# AirPurity_V1.net
KiCad netlist of a schematic drawn in Altium Designer
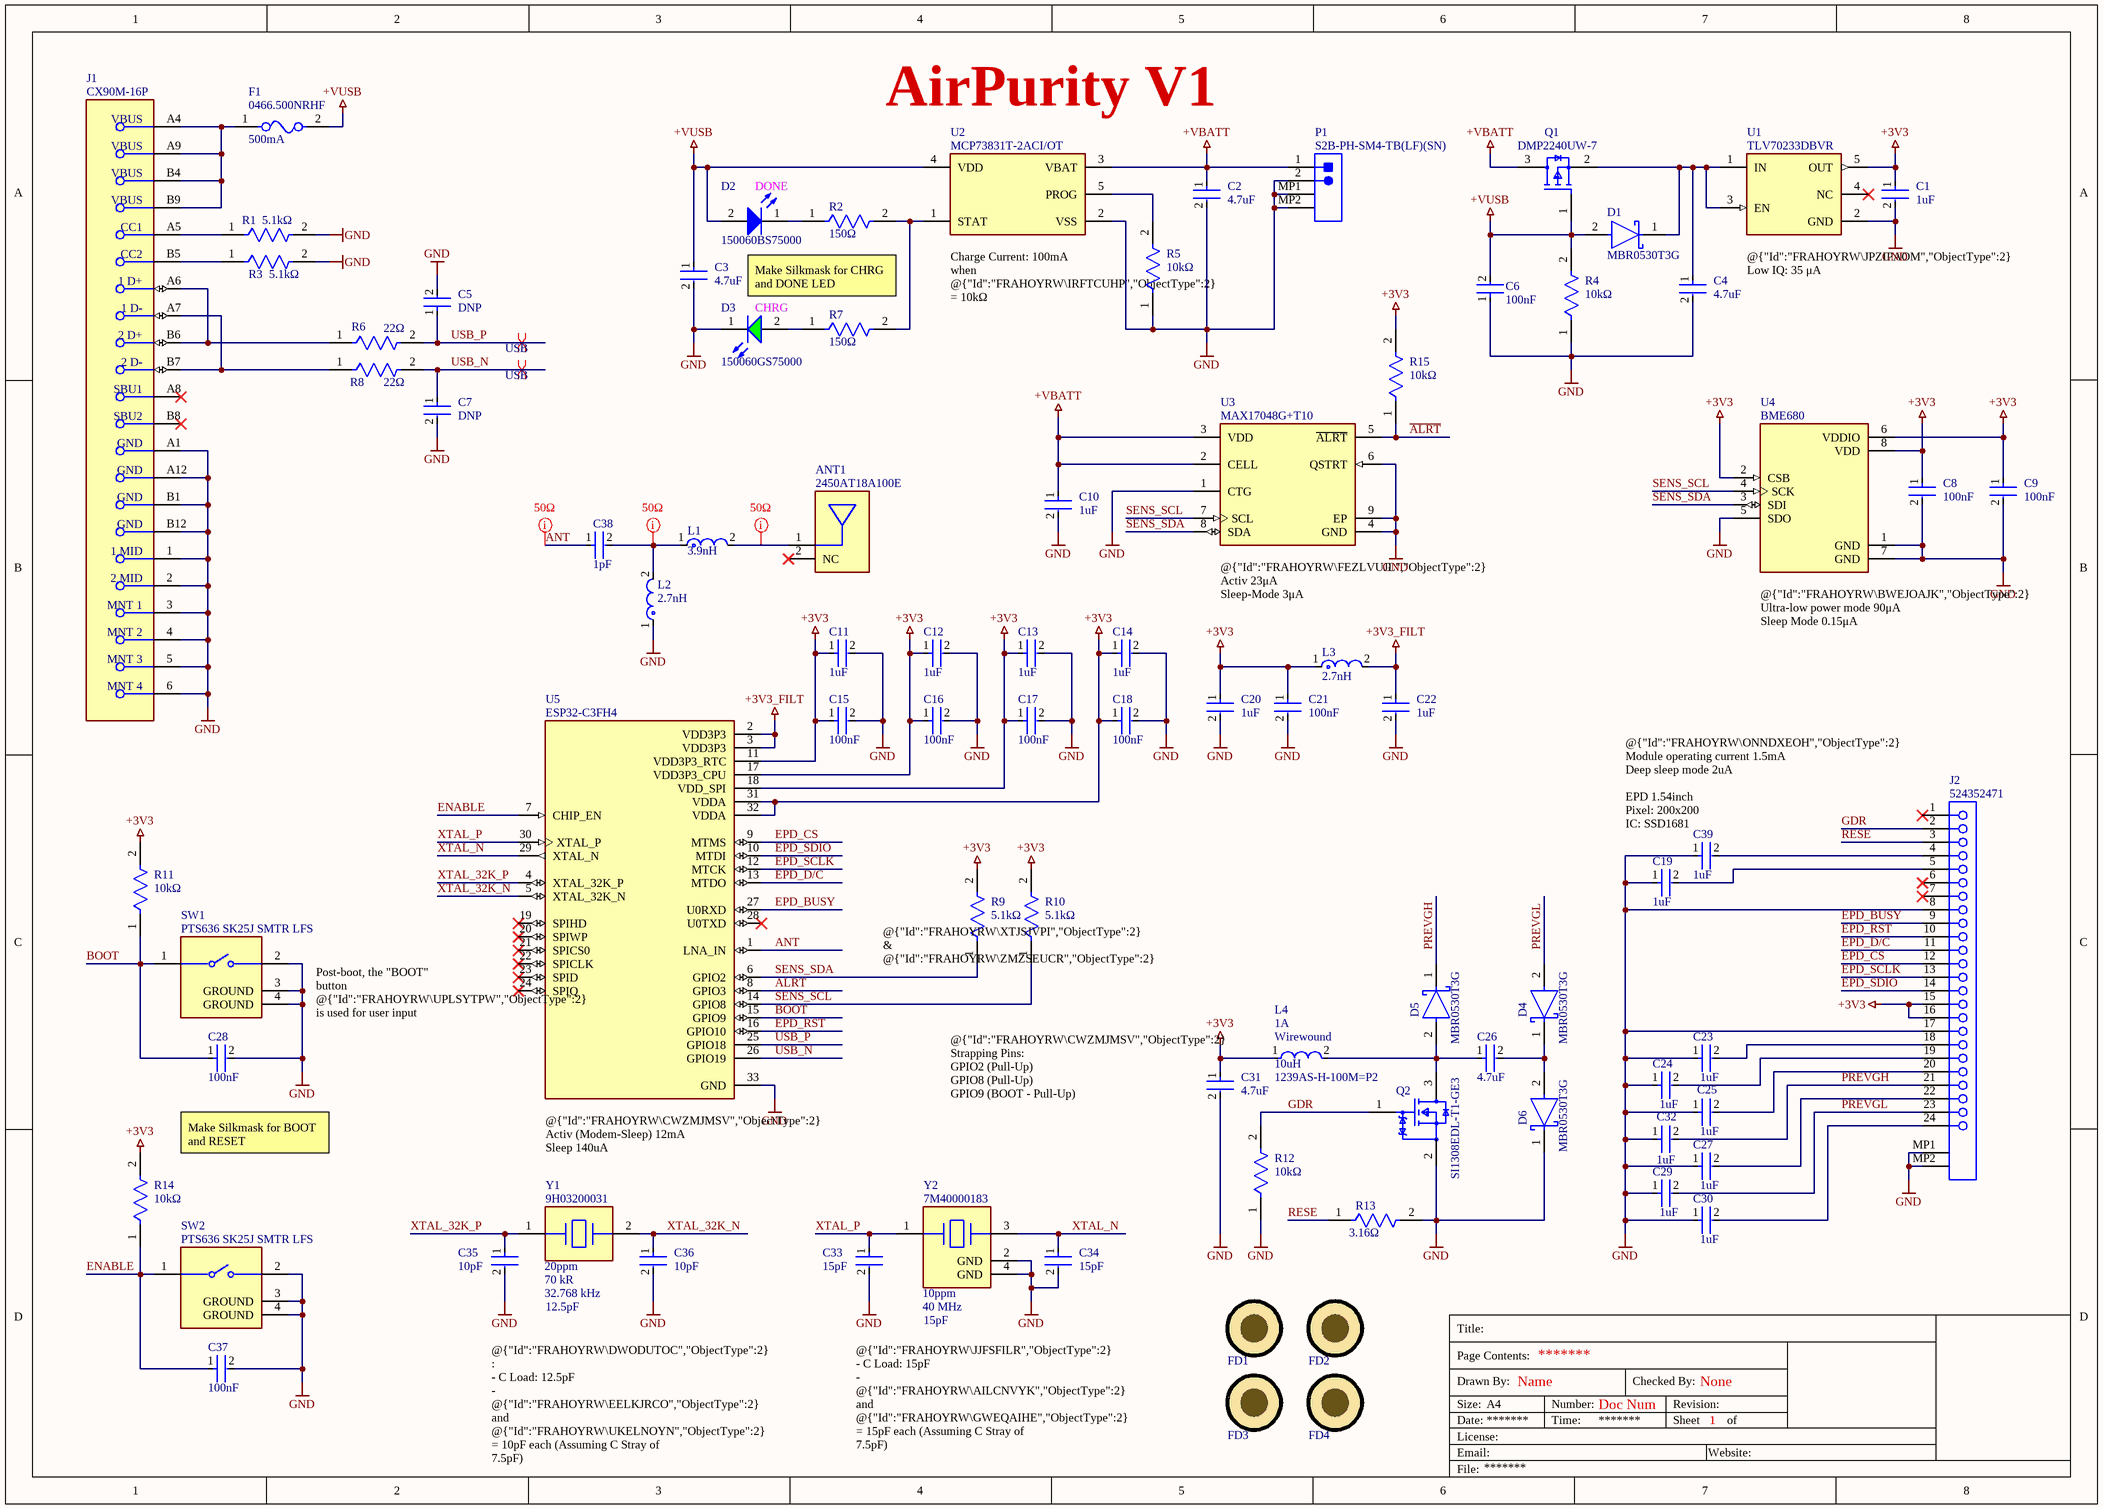
[diagram p0: AirPurity_V1.SchDoc]

(export (version "E")
  (design (tool "Eeschema 10.0.6"))
  (components
    (comp (ref "ANT1")
      (value "2450AT18A100")
      (footprint "FP-2450AT18A0100001E-MFG")
      (description "Chip Antenna 0.5dBi 2.4GHz 2W 1206")
      (fields
        (field (name "LCSC PART NUMBER") "C89334")
        (field (name "MANUFACTURER PART NUMBER") "2450AT18A100E")
      )
      (libsource (lib "Library") (part "2450AT18A100"))
    )
    (comp (ref "C1")
      (value "GRM155R61E105KA12D")
      (footprint "GRM155-0402-MFG")
      (description "1uF X5R 0402 Multilayer Ceramic Capacitor")
      (fields (field (name "LCSC PART NUMBER") "C77009") (field (name "CAPACITANCE") "1uF"))
      (libsource (lib "Library") (part "GRM155R61E105KA12D"))
    )
    (comp (ref "C2")
      (value "GRM155R61E475ME15D")
      (footprint "GRM155-0402-MFG")
      (description "4.7uF X5R 0402 Multilayer Ceramic Capacitor")
      (fields (field (name "LCSC PART NUMBER") "C2858031") (field (name "CAPACITANCE") "4.7uF"))
      (libsource (lib "Library") (part "GRM155R61E475ME15D"))
    )
    (comp (ref "C3")
      (value "GRM155R61E475ME15D")
      (footprint "GRM155-0402-MFG")
      (description "4.7uF X5R 0402 Multilayer Ceramic Capacitor")
      (fields (field (name "LCSC PART NUMBER") "C2858031") (field (name "CAPACITANCE") "4.7uF"))
      (libsource (lib "Library") (part "GRM155R61E475ME15D"))
    )
    (comp (ref "C4")
      (value "GRM155R61E475ME15D")
      (footprint "GRM155-0402-MFG")
      (description "4.7uF X5R 0402 Multilayer Ceramic Capacitor")
      (fields (field (name "LCSC PART NUMBER") "C2858031") (field (name "CAPACITANCE") "4.7uF"))
      (libsource (lib "Library") (part "GRM155R61E475ME15D"))
    )
    (comp (ref "C5")
      (value "GRM0335C1H150FA01D")
      (footprint "GRM033-0201-MFG")
      (description "15pF C0G 0201 Multilayer Ceramic Capacitor")
      (fields (field (name "LCSC PART NUMBER") "C237567") (field (name "CAPACITANCE") "DNP"))
      (libsource (lib "Library") (part "GRM0335C1H150FA01D"))
    )
    (comp (ref "C6")
      (value "GRM033R61A104KE15D")
      (footprint "GRM033-0201-MFG")
      (description "100nF X5R 0201 Multilayer Ceramic Capacitor")
      (fields (field (name "LCSC PART NUMBER") "C76934") (field (name "CAPACITANCE") "100nF"))
      (libsource (lib "Library") (part "GRM033R61A104KE15D"))
    )
    (comp (ref "C7")
      (value "GRM0335C1H150FA01D")
      (footprint "GRM033-0201-MFG")
      (description "15pF C0G 0201 Multilayer Ceramic Capacitor")
      (fields (field (name "LCSC PART NUMBER") "C237567") (field (name "CAPACITANCE") "DNP"))
      (libsource (lib "Library") (part "GRM0335C1H150FA01D"))
    )
    (comp (ref "C8")
      (value "GRM033R61A104KE15D")
      (footprint "GRM033-0201-MFG")
      (description "100nF X5R 0201 Multilayer Ceramic Capacitor")
      (fields (field (name "LCSC PART NUMBER") "C76934") (field (name "CAPACITANCE") "100nF"))
      (libsource (lib "Library") (part "GRM033R61A104KE15D"))
    )
    (comp (ref "C9")
      (value "GRM033R61A104KE15D")
      (footprint "GRM033-0201-MFG")
      (description "100nF X5R 0201 Multilayer Ceramic Capacitor")
      (fields (field (name "LCSC PART NUMBER") "C76934") (field (name "CAPACITANCE") "100nF"))
      (libsource (lib "Library") (part "GRM033R61A104KE15D"))
    )
    (comp (ref "C10")
      (value "GRM155R61E105KA12D")
      (footprint "GRM155-0402-MFG")
      (description "1uF X5R 0402 Multilayer Ceramic Capacitor")
      (fields (field (name "LCSC PART NUMBER") "C77009") (field (name "CAPACITANCE") "1uF"))
      (libsource (lib "Library") (part "GRM155R61E105KA12D"))
    )
    (comp (ref "C11")
      (value "GRM155R61E105KA12D")
      (footprint "GRM155-0402-MFG")
      (description "1uF X5R 0402 Multilayer Ceramic Capacitor")
      (fields (field (name "LCSC PART NUMBER") "C77009") (field (name "CAPACITANCE") "1uF"))
      (libsource (lib "Library") (part "GRM155R61E105KA12D"))
    )
    (comp (ref "C12")
      (value "GRM155R61E105KA12D")
      (footprint "GRM155-0402-MFG")
      (description "1uF X5R 0402 Multilayer Ceramic Capacitor")
      (fields (field (name "LCSC PART NUMBER") "C77009") (field (name "CAPACITANCE") "1uF"))
      (libsource (lib "Library") (part "GRM155R61E105KA12D"))
    )
    (comp (ref "C13")
      (value "GRM155R61E105KA12D")
      (footprint "GRM155-0402-MFG")
      (description "1uF X5R 0402 Multilayer Ceramic Capacitor")
      (fields (field (name "LCSC PART NUMBER") "C77009") (field (name "CAPACITANCE") "1uF"))
      (libsource (lib "Library") (part "GRM155R61E105KA12D"))
    )
    (comp (ref "C14")
      (value "GRM155R61E105KA12D")
      (footprint "GRM155-0402-MFG")
      (description "1uF X5R 0402 Multilayer Ceramic Capacitor")
      (fields (field (name "LCSC PART NUMBER") "C77009") (field (name "CAPACITANCE") "1uF"))
      (libsource (lib "Library") (part "GRM155R61E105KA12D"))
    )
    (comp (ref "C15")
      (value "GRM033R61A104KE15D")
      (footprint "GRM033-0201-MFG")
      (description "100nF X5R 0201 Multilayer Ceramic Capacitor")
      (fields (field (name "LCSC PART NUMBER") "C76934") (field (name "CAPACITANCE") "100nF"))
      (libsource (lib "Library") (part "GRM033R61A104KE15D"))
    )
    (comp (ref "C16")
      (value "GRM033R61A104KE15D")
      (footprint "GRM033-0201-MFG")
      (description "100nF X5R 0201 Multilayer Ceramic Capacitor")
      (fields (field (name "LCSC PART NUMBER") "C76934") (field (name "CAPACITANCE") "100nF"))
      (libsource (lib "Library") (part "GRM033R61A104KE15D"))
    )
    (comp (ref "C17")
      (value "GRM033R61A104KE15D")
      (footprint "GRM033-0201-MFG")
      (description "100nF X5R 0201 Multilayer Ceramic Capacitor")
      (fields (field (name "LCSC PART NUMBER") "C76934") (field (name "CAPACITANCE") "100nF"))
      (libsource (lib "Library") (part "GRM033R61A104KE15D"))
    )
    (comp (ref "C18")
      (value "GRM033R61A104KE15D")
      (footprint "GRM033-0201-MFG")
      (description "100nF X5R 0201 Multilayer Ceramic Capacitor")
      (fields (field (name "LCSC PART NUMBER") "C76934") (field (name "CAPACITANCE") "100nF"))
      (libsource (lib "Library") (part "GRM033R61A104KE15D"))
    )
    (comp (ref "C19")
      (value "GRM155R61E105KA12D")
      (footprint "GRM155-0402-MFG")
      (description "1uF X5R 0402 Multilayer Ceramic Capacitor")
      (fields (field (name "LCSC PART NUMBER") "C77009") (field (name "CAPACITANCE") "1uF"))
      (libsource (lib "Library") (part "GRM155R61E105KA12D"))
    )
    (comp (ref "C20")
      (value "GRM155R61E105KA12D")
      (footprint "GRM155-0402-MFG")
      (description "1uF X5R 0402 Multilayer Ceramic Capacitor")
      (fields (field (name "LCSC PART NUMBER") "C77009") (field (name "CAPACITANCE") "1uF"))
      (libsource (lib "Library") (part "GRM155R61E105KA12D"))
    )
    (comp (ref "C21")
      (value "GRM033R61A104KE15D")
      (footprint "GRM033-0201-MFG")
      (description "100nF X5R 0201 Multilayer Ceramic Capacitor")
      (fields (field (name "LCSC PART NUMBER") "C76934") (field (name "CAPACITANCE") "100nF"))
      (libsource (lib "Library") (part "GRM033R61A104KE15D"))
    )
    (comp (ref "C22")
      (value "GRM155R61E105KA12D")
      (footprint "GRM155-0402-MFG")
      (description "1uF X5R 0402 Multilayer Ceramic Capacitor")
      (fields (field (name "LCSC PART NUMBER") "C77009") (field (name "CAPACITANCE") "1uF"))
      (libsource (lib "Library") (part "GRM155R61E105KA12D"))
    )
    (comp (ref "C23")
      (value "GRM155R61E105KA12D")
      (footprint "GRM155-0402-MFG")
      (description "1uF X5R 0402 Multilayer Ceramic Capacitor")
      (fields (field (name "LCSC PART NUMBER") "C77009") (field (name "CAPACITANCE") "1uF"))
      (libsource (lib "Library") (part "GRM155R61E105KA12D"))
    )
    (comp (ref "C24")
      (value "GRM155R61E105KA12D")
      (footprint "GRM155-0402-MFG")
      (description "1uF X5R 0402 Multilayer Ceramic Capacitor")
      (fields (field (name "LCSC PART NUMBER") "C77009") (field (name "CAPACITANCE") "1uF"))
      (libsource (lib "Library") (part "GRM155R61E105KA12D"))
    )
    (comp (ref "C25")
      (value "GRM155R61E105KA12D")
      (footprint "GRM155-0402-MFG")
      (description "1uF X5R 0402 Multilayer Ceramic Capacitor")
      (fields (field (name "LCSC PART NUMBER") "C77009") (field (name "CAPACITANCE") "1uF"))
      (libsource (lib "Library") (part "GRM155R61E105KA12D"))
    )
    (comp (ref "C26")
      (value "GRM155R61E475ME15D")
      (footprint "GRM155-0402-MFG")
      (description "4.7uF X5R 0402 Multilayer Ceramic Capacitor")
      (fields (field (name "LCSC PART NUMBER") "C2858031") (field (name "CAPACITANCE") "4.7uF"))
      (libsource (lib "Library") (part "GRM155R61E475ME15D"))
    )
    (comp (ref "C27")
      (value "GRM155R61E105KA12D")
      (footprint "GRM155-0402-MFG")
      (description "1uF X5R 0402 Multilayer Ceramic Capacitor")
      (fields (field (name "LCSC PART NUMBER") "C77009") (field (name "CAPACITANCE") "1uF"))
      (libsource (lib "Library") (part "GRM155R61E105KA12D"))
    )
    (comp (ref "C28")
      (value "GRM033R61A104KE15D")
      (footprint "GRM033-0201-MFG")
      (description "100nF X5R 0201 Multilayer Ceramic Capacitor")
      (fields (field (name "LCSC PART NUMBER") "C76934") (field (name "CAPACITANCE") "100nF"))
      (libsource (lib "Library") (part "GRM033R61A104KE15D"))
    )
    (comp (ref "C29")
      (value "GRM155R61E105KA12D")
      (footprint "GRM155-0402-MFG")
      (description "1uF X5R 0402 Multilayer Ceramic Capacitor")
      (fields (field (name "LCSC PART NUMBER") "C77009") (field (name "CAPACITANCE") "1uF"))
      (libsource (lib "Library") (part "GRM155R61E105KA12D"))
    )
    (comp (ref "C30")
      (value "GRM155R61E105KA12D")
      (footprint "GRM155-0402-MFG")
      (description "1uF X5R 0402 Multilayer Ceramic Capacitor")
      (fields (field (name "LCSC PART NUMBER") "C77009") (field (name "CAPACITANCE") "1uF"))
      (libsource (lib "Library") (part "GRM155R61E105KA12D"))
    )
    (comp (ref "C31")
      (value "GRM155R61E475ME15D")
      (footprint "GRM155-0402-MFG")
      (description "4.7uF X5R 0402 Multilayer Ceramic Capacitor")
      (fields (field (name "LCSC PART NUMBER") "C2858031") (field (name "CAPACITANCE") "4.7uF"))
      (libsource (lib "Library") (part "GRM155R61E475ME15D"))
    )
    (comp (ref "C32")
      (value "GRM155R61E105KA12D")
      (footprint "GRM155-0402-MFG")
      (description "1uF X5R 0402 Multilayer Ceramic Capacitor")
      (fields (field (name "LCSC PART NUMBER") "C77009") (field (name "CAPACITANCE") "1uF"))
      (libsource (lib "Library") (part "GRM155R61E105KA12D"))
    )
    (comp (ref "C33")
      (value "GRM0335C1H150FA01D")
      (footprint "GRM033-0201-MFG")
      (description "15pF C0G 0201 Multilayer Ceramic Capacitor")
      (fields (field (name "LCSC PART NUMBER") "C237567") (field (name "CAPACITANCE") "15pF"))
      (libsource (lib "Library") (part "GRM0335C1H150FA01D"))
    )
    (comp (ref "C34")
      (value "GRM0335C1H150FA01D")
      (footprint "GRM033-0201-MFG")
      (description "15pF C0G 0201 Multilayer Ceramic Capacitor")
      (fields (field (name "LCSC PART NUMBER") "C237567") (field (name "CAPACITANCE") "15pF"))
      (libsource (lib "Library") (part "GRM0335C1H150FA01D"))
    )
    (comp (ref "C35")
      (value "GRM0335C1H100JA01D")
      (footprint "GRM033-0201-MFG")
      (description "10pF C0G 0201 Multilayer Ceramic Capacitor")
      (fields (field (name "LCSC PART NUMBER") "C76921") (field (name "CAPACITANCE") "10pF"))
      (libsource (lib "Library") (part "GRM0335C1H100JA01D"))
    )
    (comp (ref "C36")
      (value "GRM0335C1H100JA01D")
      (footprint "GRM033-0201-MFG")
      (description "10pF C0G 0201 Multilayer Ceramic Capacitor")
      (fields (field (name "LCSC PART NUMBER") "C76921") (field (name "CAPACITANCE") "10pF"))
      (libsource (lib "Library") (part "GRM0335C1H100JA01D"))
    )
    (comp (ref "C37")
      (value "GRM033R61A104KE15D")
      (footprint "GRM033-0201-MFG")
      (description "100nF X5R 0201 Multilayer Ceramic Capacitor")
      (fields (field (name "LCSC PART NUMBER") "C76934") (field (name "CAPACITANCE") "100nF"))
      (libsource (lib "Library") (part "GRM033R61A104KE15D"))
    )
    (comp (ref "C38")
      (value "GRM0335C1H1R0BA01D")
      (footprint "GRM033-0201-MFG")
      (description "1pF C0G 0201 Multilayer Ceramic Capacitor")
      (fields (field (name "LCSC PART NUMBER") "C85893") (field (name "CAPACITANCE") "1pF"))
      (libsource (lib "Library") (part "GRM0335C1H1R0BA01D"))
    )
    (comp (ref "C39")
      (value "GRM155R61E105KA12D")
      (footprint "GRM155-0402-MFG")
      (description "1uF X5R 0402 Multilayer Ceramic Capacitor")
      (fields (field (name "LCSC PART NUMBER") "C77009") (field (name "CAPACITANCE") "1uF"))
      (libsource (lib "Library") (part "GRM155R61E105KA12D"))
    )
    (comp (ref "D1")
      (value "MBR0530T3G")
      (footprint "425-04-MFG")
      (description "Schottky Barrier Diodes")
      (fields
        (field (name "LCSC PART NUMBER") "C236079")
        (field (name "MANUFACTURER PART NUMBER") "MBR0530T3G")
      )
      (libsource (lib "Library") (part "MBR0530T3G"))
    )
    (comp (ref "D2")
      (value "150060BS75000")
      (footprint "0603_150060xx75000")
      (description "LED Blue 3.2V 0603")
      (fields
        (field (name "LCSC PART NUMBER") "C5197644")
        (field (name "MANUFACTURER PART NUMBER") "150060BS75000")
      )
      (libsource (lib "Library") (part "150060BS75000"))
    )
    (comp (ref "D3")
      (value "150060GS75000")
      (footprint "0603_150060xx75000")
      (description "LED Emerald 3.2V 0603")
      (fields
        (field (name "LCSC PART NUMBER") "C5252984")
        (field (name "MANUFACTURER PART NUMBER") "150060GS75000")
      )
      (libsource (lib "Library") (part "150060GS75000"))
    )
    (comp (ref "D4")
      (value "MBR0530T3G")
      (footprint "425-04-MFG")
      (description "Schottky Barrier Diodes")
      (fields
        (field (name "LCSC PART NUMBER") "C236079")
        (field (name "MANUFACTURER PART NUMBER") "MBR0530T3G")
      )
      (libsource (lib "Library") (part "MBR0530T3G"))
    )
    (comp (ref "D5")
      (value "MBR0530T3G")
      (footprint "425-04-MFG")
      (description "Schottky Barrier Diodes")
      (fields
        (field (name "LCSC PART NUMBER") "C236079")
        (field (name "MANUFACTURER PART NUMBER") "MBR0530T3G")
      )
      (libsource (lib "Library") (part "MBR0530T3G"))
    )
    (comp (ref "D6")
      (value "MBR0530T3G")
      (footprint "425-04-MFG")
      (description "Schottky Barrier Diodes")
      (fields
        (field (name "LCSC PART NUMBER") "C236079")
        (field (name "MANUFACTURER PART NUMBER") "MBR0530T3G")
      )
      (libsource (lib "Library") (part "MBR0530T3G"))
    )
    (comp (ref "F1")
      (value "0466.500NRHF")
      (footprint "0466-MFG")
      (description "Fuse 500mA")
      (fields
        (field (name "LCSC PART NUMBER") "C151133")
        (field (name "MANUFACTURER PART NUMBER") "0466.500NRHF")
        (field (name "CURRENT") "500mA")
      )
      (libsource (lib "Library") (part "0466.500NRHF"))
    )
    (comp (ref "FD1")
      (value "Fiducial")
      (footprint "FIDUCIAL-1MM")
      (libsource (lib "Library") (part "Fiducial"))
    )
    (comp (ref "FD2")
      (value "Fiducial")
      (footprint "FIDUCIAL-1MM")
      (libsource (lib "Library") (part "Fiducial"))
    )
    (comp (ref "FD3")
      (value "Fiducial")
      (footprint "FIDUCIAL-1MM")
      (libsource (lib "Library") (part "Fiducial"))
    )
    (comp (ref "FD4")
      (value "Fiducial")
      (footprint "FIDUCIAL-1MM")
      (libsource (lib "Library") (part "Fiducial"))
    )
    (comp (ref "J1")
      (value "CX90M-16P")
      (footprint "CX90M-16P-MFG")
      (description "Connector USB2.0 TYPE-C 16POS")
      (fields
        (field (name "LCSC PART NUMBER") "C2889324")
        (field (name "MANUFACTURER PART NUMBER") "CX90M-16P")
      )
      (libsource (lib "Library") (part "CX90M-16P"))
    )
    (comp (ref "J2")
      (value "524352471")
      (footprint "52435-2471")
      (description "FPC Connector, 2.0 mm, 0.5 mm, Right Angle")
      (fields
        (field (name "LCSC PART NUMBER") "C122394")
        (field (name "MANUFACTURER PART NUMBER") "524352471")
      )
      (libsource (lib "Library") (part "524352471"))
    )
    (comp (ref "L1")
      (value "LQP03TN3N9B02D")
      (footprint "LQP03TG-MFG")
      (description "Inductor 3.9nH")
      (fields (field (name "LCSC PART NUMBER") "C77115") (field (name "INDUCTANCE") "3.9nH"))
      (libsource (lib "Library") (part "LQP03TN3N9B02D"))
    )
    (comp (ref "L2")
      (value "LQP03TG2N7C02D")
      (footprint "LQP03TG-MFG")
      (description "Inductor 2.7nH")
      (fields (field (name "LCSC PART NUMBER") "C337946") (field (name "INDUCTANCE") "2.7nH"))
      (libsource (lib "Library") (part "LQP03TG2N7C02D"))
    )
    (comp (ref "L3")
      (value "LQP03TG2N7C02D")
      (footprint "LQP03TG-MFG")
      (description "Inductor 2.7nH")
      (fields (field (name "LCSC PART NUMBER") "C337946") (field (name "INDUCTANCE") "2.7nH"))
      (libsource (lib "Library") (part "LQP03TG2N7C02D"))
    )
    (comp (ref "L4")
      (value "1239AS-H-100M=P2")
      (footprint "DFE252012C-MFG")
      (description "Inductor 10uH")
      (fields
        (field (name "LCSC PART NUMBER") "C237599")
        (field (name "CURRENT RATING") "1A")
        (field (name "RESISTOR TYPE") "Wirewound")
        (field (name "INDUCTANCE") "10uH")
        (field (name "MANUFACTURER PART NUMBER") "1239AS-H-100M=P2")
      )
      (libsource (lib "Library") (part "1239AS-H-100M=P2"))
    )
    (comp (ref "P1")
      (value "S2B-PH-SM4-TB(LF)(SN)")
      (footprint "JST- S2B-PH-SM4-TB(LF)(SN)")
      (description "Male Header, Pitch 2 mm, 1 x 2 Position")
      (fields
        (field (name "LCSC PART NUMBER") "C295747")
        (field (name "MANUFACTURER PART NUMBER") "S2B-PH-SM4-TB(LF)(SN)")
      )
      (libsource (lib "Library") (part "S2B-PH-SM4-TB(LF)(SN)"))
    )
    (comp (ref "Q1")
      (value "DMP2240UW-7")
      (footprint "SOT323-MFG")
      (description "MOSFET P-Channel")
      (fields
        (field (name "LCSC PART NUMBER") "C459548")
        (field (name "MANUFACTURER PART NUMBER") "DMP2240UW-7")
      )
      (libsource (lib "Library") (part "DMP2240UW-7"))
    )
    (comp (ref "Q2")
      (value "SI1308EDL-T1-GE3")
      (footprint "5549-MFG")
      (description "MOSFET N-Channel")
      (fields
        (field (name "LCSC PART NUMBER") "C469327")
        (field (name "MANUFACTURER PART NUMBER") "SI1308EDL-T1-GE3")
      )
      (libsource (lib "Library") (part "SI1308EDL-T1-GE3"))
    )
    (comp (ref "R1")
      (value "RC0402FR-075K1L")
      (footprint "RC0402-MFG")
      (description "5.1kΩ 0402 Chip Resistor")
      (fields (field (name "LCSC PART NUMBER") "C105872") (field (name "RESISTANCE") "5.1kΩ"))
      (libsource (lib "Library") (part "RC0402FR-075K1L"))
    )
    (comp (ref "R2")
      (value "RC0402FR-07150RL")
      (footprint "RC0402-MFG")
      (description "150Ω 0402 Chip Resistor")
      (fields (field (name "LCSC PART NUMBER") "C138054") (field (name "RESISTANCE") "150Ω"))
      (libsource (lib "Library") (part "RC0402FR-07150RL"))
    )
    (comp (ref "R3")
      (value "RC0402FR-075K1L")
      (footprint "RC0402-MFG")
      (description "5.1kΩ 0402 Chip Resistor")
      (fields (field (name "LCSC PART NUMBER") "C105872") (field (name "RESISTANCE") "5.1kΩ"))
      (libsource (lib "Library") (part "RC0402FR-075K1L"))
    )
    (comp (ref "R4")
      (value "RC0402FR-0710KL")
      (footprint "RC0402-MFG")
      (description "10kΩ 0402 Chip Resistor")
      (fields (field (name "LCSC PART NUMBER") "C60490") (field (name "RESISTANCE") "10kΩ"))
      (libsource (lib "Library") (part "RC0402FR-0710KL"))
    )
    (comp (ref "R5")
      (value "RC0402FR-0710KL")
      (footprint "RC0402-MFG")
      (description "10kΩ 0402 Chip Resistor")
      (fields (field (name "LCSC PART NUMBER") "C60490") (field (name "RESISTANCE") "10kΩ"))
      (libsource (lib "Library") (part "RC0402FR-0710KL"))
    )
    (comp (ref "R6")
      (value "RC0402FR-0722RL")
      (footprint "RC0402-MFG")
      (description "22Ω 0402 Chip Resistor")
      (fields (field (name "LCSC PART NUMBER") "C114765") (field (name "RESISTANCE") "22Ω"))
      (libsource (lib "Library") (part "RC0402FR-0722RL"))
    )
    (comp (ref "R7")
      (value "RC0402FR-07150RL")
      (footprint "RC0402-MFG")
      (description "150Ω 0402 Chip Resistor")
      (fields (field (name "LCSC PART NUMBER") "C138054") (field (name "RESISTANCE") "150Ω"))
      (libsource (lib "Library") (part "RC0402FR-07150RL"))
    )
    (comp (ref "R8")
      (value "RC0402FR-0722RL")
      (footprint "RC0402-MFG")
      (description "22Ω 0402 Chip Resistor")
      (fields (field (name "LCSC PART NUMBER") "C114765") (field (name "RESISTANCE") "22Ω"))
      (libsource (lib "Library") (part "RC0402FR-0722RL"))
    )
    (comp (ref "R9")
      (value "RC0402FR-075K1L")
      (footprint "RC0402-MFG")
      (description "5.1kΩ 0402 Chip Resistor")
      (fields (field (name "LCSC PART NUMBER") "C105872") (field (name "RESISTANCE") "5.1kΩ"))
      (libsource (lib "Library") (part "RC0402FR-075K1L"))
    )
    (comp (ref "R10")
      (value "RC0402FR-075K1L")
      (footprint "RC0402-MFG")
      (description "5.1kΩ 0402 Chip Resistor")
      (fields (field (name "LCSC PART NUMBER") "C105872") (field (name "RESISTANCE") "5.1kΩ"))
      (libsource (lib "Library") (part "RC0402FR-075K1L"))
    )
    (comp (ref "R11")
      (value "RC0402FR-0710KL")
      (footprint "RC0402-MFG")
      (description "10kΩ 0402 Chip Resistor")
      (fields (field (name "LCSC PART NUMBER") "C60490") (field (name "RESISTANCE") "10kΩ"))
      (libsource (lib "Library") (part "RC0402FR-0710KL"))
    )
    (comp (ref "R12")
      (value "RC0402FR-0710KL")
      (footprint "RC0402-MFG")
      (description "10kΩ 0402 Chip Resistor")
      (fields (field (name "LCSC PART NUMBER") "C60490") (field (name "RESISTANCE") "10kΩ"))
      (libsource (lib "Library") (part "RC0402FR-0710KL"))
    )
    (comp (ref "R13")
      (value "RC0402FR-073R16L")
      (footprint "RC0402-MFG")
      (description "3.16Ω 0402 Chip Resistor")
      (fields (field (name "LCSC PART NUMBER") "C477688") (field (name "RESISTANCE") "3.16Ω"))
      (libsource (lib "Library") (part "RC0402FR-073R16L"))
    )
    (comp (ref "R14")
      (value "RC0402FR-0710KL")
      (footprint "RC0402-MFG")
      (description "10kΩ 0402 Chip Resistor")
      (fields (field (name "LCSC PART NUMBER") "C60490") (field (name "RESISTANCE") "10kΩ"))
      (libsource (lib "Library") (part "RC0402FR-0710KL"))
    )
    (comp (ref "R15")
      (value "RC0402FR-0710KL")
      (footprint "RC0402-MFG")
      (description "10kΩ 0402 Chip Resistor")
      (fields (field (name "LCSC PART NUMBER") "C60490") (field (name "RESISTANCE") "10kΩ"))
      (libsource (lib "Library") (part "RC0402FR-0710KL"))
    )
    (comp (ref "SW1")
      (value "PTS636 SK25J SMTR LFS")
      (footprint "PTS636_SKG25_SMTR_LFS-MFG")
      (description "Tactile Switch SPST")
      (fields
        (field (name "LCSC PART NUMBER") "C2800965")
        (field (name "MANUFACTURER PART NUMBER") "PTS636 SK25J SMTR LFS")
      )
      (libsource (lib "Library") (part "PTS636 SK25J SMTR LFS"))
    )
    (comp (ref "SW2")
      (value "PTS636 SK25J SMTR LFS")
      (footprint "PTS636_SKG25_SMTR_LFS-MFG")
      (description "Tactile Switch SPST")
      (fields
        (field (name "LCSC PART NUMBER") "C2800965")
        (field (name "MANUFACTURER PART NUMBER") "PTS636 SK25J SMTR LFS")
      )
      (libsource (lib "Library") (part "PTS636 SK25J SMTR LFS"))
    )
    (comp (ref "U1")
      (value "TLV70233DBVR")
      (footprint "DBV0005A-MFG")
      (description "LDO Voltage Regulators 300mALow IQLDO Reg")
      (fields
        (field (name "LCSC PART NUMBER") "C26833")
        (field (name "MANUFACTURER PART NUMBER") "TLV70233DBVR")
      )
      (libsource (lib "Library") (part "TLV70233DBVR"))
    )
    (comp (ref "U2")
      (value "MCP73831T-2ACI/OT")
      (footprint "SOT23-5LD-PL-1-MFG")
      (description "IC Controller LI-ION 4.2V")
      (fields
        (field (name "LCSC PART NUMBER") "C424093")
        (field (name "MANUFACTURER PART NUMBER") "MCP73831T-2ACI/OT")
      )
      (libsource (lib "Library") (part "MCP73831T-2ACI/OT"))
    )
    (comp (ref "U3")
      (value "MAX17048G+T10")
      (footprint "T822-3-MFG")
      (description "Fuel Gauge LI-ION")
      (fields
        (field (name "LCSC PART NUMBER") "C2682616")
        (field (name "MANUFACTURER PART NUMBER") "MAX17048G+T10")
      )
      (libsource (lib "Library") (part "MAX17048G+T10"))
    )
    (comp (ref "U4")
      (value "BME680")
      (footprint "PSON80P300X300X100-8N")
      (description "Gas, Humidity, Pressure, Temperature Sensor I²C")
      (fields (field (name "LCSC PART NUMBER") "C125972") (field (name "MANUFACTURER PART NUMBER") "BME680"))
      (libsource (lib "Library") (part "BME680"))
    )
    (comp (ref "U5")
      (value "ESP32-C3FH4")
      (footprint "QFN50P500X500X90-33N")
      (fields
        (field (name "LCSC PART NUMBER") "C2858491")
        (field (name "MANUFACTURER PART NUMBER") "ESP32-C3FH4")
      )
      (libsource (lib "Library") (part "ESP32-C3FH4"))
    )
    (comp (ref "Y1")
      (value "9H03200031")
      (footprint "ABS10")
      (description "Crystal 32.768 kHz")
      (fields
        (field (name "LCSC PART NUMBER") "C90944")
        (field (name "FREQUENCY TOLERANCE") "20ppm")
        (field (name "EQUIVALENT SERIES RESISTANCE") "70 kR")
        (field (name "FREQUENCY") "32.768 kHz")
        (field (name "MANUFACTURER PART NUMBER") "9H03200031")
        (field (name "LOAD CAPACITANCE") "12.5pF")
      )
      (libsource (lib "Library") (part "9H03200031"))
    )
    (comp (ref "Y2")
      (value "7M40000183")
      (footprint "ABM8")
      (description "Crystal 40 MHz")
      (fields
        (field (name "LCSC PART NUMBER") "C331598")
        (field (name "FREQUENCY TOLERANCE") "10ppm")
        (field (name "FREQUENCY") "40 MHz")
        (field (name "MANUFACTURER PART NUMBER") "7M40000183")
        (field (name "LOAD CAPACITANCE") "15pF")
      )
      (libsource (lib "Library") (part "7M40000183"))
    )
  )
  (nets
    (net (code "1") (name "+3V3") (class "Default")
      (node (ref "C1") (pin "1") (pinfunction "1_1") (pintype "passive"))
      (node (ref "C11") (pin "1") (pinfunction "1_1") (pintype "passive"))
      (node (ref "C12") (pin "1") (pinfunction "1_1") (pintype "passive"))
      (node (ref "C13") (pin "1") (pinfunction "1_1") (pintype "passive"))
      (node (ref "C14") (pin "1") (pinfunction "1_1") (pintype "passive"))
      (node (ref "C15") (pin "1") (pinfunction "1_1") (pintype "passive"))
      (node (ref "C16") (pin "1") (pinfunction "1_1") (pintype "passive"))
      (node (ref "C17") (pin "1") (pinfunction "1_1") (pintype "passive"))
      (node (ref "C18") (pin "1") (pinfunction "1_1") (pintype "passive"))
      (node (ref "C20") (pin "1") (pinfunction "1_1") (pintype "passive"))
      (node (ref "C21") (pin "1") (pinfunction "1_1") (pintype "passive"))
      (node (ref "C31") (pin "1") (pinfunction "1_1") (pintype "passive"))
      (node (ref "C8") (pin "1") (pinfunction "1_1") (pintype "passive"))
      (node (ref "C9") (pin "1") (pinfunction "1_1") (pintype "passive"))
      (node (ref "J2") (pin "15") (pinfunction "15_15") (pintype "passive"))
      (node (ref "J2") (pin "16") (pinfunction "16_16") (pintype "passive"))
      (node (ref "L3") (pin "1") (pinfunction "1_1") (pintype "passive"))
      (node (ref "L4") (pin "1") (pinfunction "1_1") (pintype "passive"))
      (node (ref "R10") (pin "2") (pinfunction "2_2") (pintype "passive"))
      (node (ref "R11") (pin "2") (pinfunction "2_2") (pintype "passive"))
      (node (ref "R14") (pin "2") (pinfunction "2_2") (pintype "passive"))
      (node (ref "R15") (pin "2") (pinfunction "2_2") (pintype "passive"))
      (node (ref "R9") (pin "2") (pinfunction "2_2") (pintype "passive"))
      (node (ref "U1") (pin "5") (pinfunction "OUT_5") (pintype "output"))
      (node (ref "U4") (pin "2") (pinfunction "CSB_2") (pintype "input"))
      (node (ref "U4") (pin "6") (pinfunction "VDDIO_6") (pintype "passive"))
      (node (ref "U4") (pin "8") (pinfunction "VDD_8") (pintype "passive"))
      (node (ref "U5") (pin "11") (pinfunction "VDD3P3_RTC_11") (pintype "passive"))
      (node (ref "U5") (pin "17") (pinfunction "VDD3P3_CPU_17") (pintype "passive"))
      (node (ref "U5") (pin "18") (pinfunction "VDD_SPI_18") (pintype "passive"))
      (node (ref "U5") (pin "31") (pinfunction "VDDA_31") (pintype "passive"))
      (node (ref "U5") (pin "32") (pinfunction "VDDA_32") (pintype "passive"))
    )
    (net (code "2") (name "+3V3_FILT") (class "Default")
      (node (ref "C22") (pin "1") (pinfunction "1_1") (pintype "passive"))
      (node (ref "L3") (pin "2") (pinfunction "2_2") (pintype "passive"))
      (node (ref "U5") (pin "2") (pinfunction "VDD3P3_2") (pintype "passive"))
      (node (ref "U5") (pin "3") (pinfunction "VDD3P3_3") (pintype "passive"))
    )
    (net (code "3") (name "+VBATT") (class "Default")
      (node (ref "C10") (pin "1") (pinfunction "1_1") (pintype "passive"))
      (node (ref "C2") (pin "1") (pinfunction "1_1") (pintype "passive"))
      (node (ref "P1") (pin "1") (pinfunction "1_1") (pintype "passive"))
      (node (ref "Q1") (pin "3") (pinfunction "D_3") (pintype "passive"))
      (node (ref "U2") (pin "3") (pinfunction "VBAT_3") (pintype "power_in"))
      (node (ref "U3") (pin "2") (pinfunction "CELL_2") (pintype "power_in"))
      (node (ref "U3") (pin "3") (pinfunction "VDD_3") (pintype "power_in"))
    )
    (net (code "4") (name "+VUSB") (class "Default")
      (node (ref "C3") (pin "1") (pinfunction "1_1") (pintype "passive"))
      (node (ref "C6") (pin "2") (pinfunction "2_2") (pintype "passive"))
      (node (ref "D1") (pin "2") (pinfunction "A_2") (pintype "passive"))
      (node (ref "D2") (pin "2") (pinfunction "A_2") (pintype "passive"))
      (node (ref "F1") (pin "2") (pinfunction "2_2") (pintype "passive"))
      (node (ref "Q1") (pin "1") (pinfunction "G_1") (pintype "passive"))
      (node (ref "R4") (pin "2") (pinfunction "2_2") (pintype "passive"))
      (node (ref "U2") (pin "4") (pinfunction "VDD_4") (pintype "power_in"))
    )
    (net (code "5") (name "/ANT") (class "Default")
      (node (ref "C38") (pin "1") (pinfunction "1_1") (pintype "passive"))
      (node (ref "U5") (pin "1") (pinfunction "LNA_IN_1") (pintype "bidirectional"))
    )
    (net (code "6") (name "/BOOT") (class "Default")
      (node (ref "C28") (pin "1") (pinfunction "1_1") (pintype "passive"))
      (node (ref "R11") (pin "1") (pinfunction "1_1") (pintype "passive"))
      (node (ref "SW1") (pin "1") (pinfunction "1_1") (pintype "passive"))
      (node (ref "U5") (pin "15") (pinfunction "GPIO9_15") (pintype "bidirectional"))
    )
    (net (code "7") (name "/ENABLE") (class "Default")
      (node (ref "C37") (pin "1") (pinfunction "1_1") (pintype "passive"))
      (node (ref "R14") (pin "1") (pinfunction "1_1") (pintype "passive"))
      (node (ref "SW2") (pin "1") (pinfunction "1_1") (pintype "passive"))
      (node (ref "U5") (pin "7") (pinfunction "CHIP_EN_7") (pintype "input"))
    )
    (net (code "8") (name "/EPD_BUSY") (class "Default")
      (node (ref "J2") (pin "9") (pinfunction "9_9") (pintype "passive"))
      (node (ref "U5") (pin "27") (pinfunction "U0RXD_27") (pintype "bidirectional"))
    )
    (net (code "9") (name "/EPD_CS") (class "Default")
      (node (ref "J2") (pin "12") (pinfunction "12_12") (pintype "passive"))
      (node (ref "U5") (pin "9") (pinfunction "MTMS_9") (pintype "bidirectional"))
    )
    (net (code "10") (name "/EPD_D{slash}C") (class "Default")
      (node (ref "J2") (pin "11") (pinfunction "11_11") (pintype "passive"))
      (node (ref "U5") (pin "13") (pinfunction "MTDO_13") (pintype "bidirectional"))
    )
    (net (code "11") (name "/EPD_RST") (class "Default")
      (node (ref "J2") (pin "10") (pinfunction "10_10") (pintype "passive"))
      (node (ref "U5") (pin "16") (pinfunction "GPIO10_16") (pintype "bidirectional"))
    )
    (net (code "12") (name "/EPD_SCLK") (class "Default")
      (node (ref "J2") (pin "13") (pinfunction "13_13") (pintype "passive"))
      (node (ref "U5") (pin "12") (pinfunction "MTCK_12") (pintype "bidirectional"))
    )
    (net (code "13") (name "/EPD_SDIO") (class "Default")
      (node (ref "J2") (pin "14") (pinfunction "14_14") (pintype "passive"))
      (node (ref "U5") (pin "10") (pinfunction "MTDI_10") (pintype "bidirectional"))
    )
    (net (code "14") (name "/GDR") (class "Default")
      (node (ref "J2") (pin "2") (pinfunction "2_2") (pintype "passive"))
      (node (ref "Q2") (pin "1") (pinfunction "G_1") (pintype "passive"))
      (node (ref "R12") (pin "2") (pinfunction "2_2") (pintype "passive"))
    )
    (net (code "15") (name "/PREVGH") (class "Default")
      (node (ref "C32") (pin "2") (pinfunction "2_2") (pintype "passive"))
      (node (ref "D5") (pin "1") (pinfunction "C_1") (pintype "passive"))
      (node (ref "J2") (pin "21") (pinfunction "21_21") (pintype "passive"))
    )
    (net (code "16") (name "/PREVGL") (class "Default")
      (node (ref "C29") (pin "2") (pinfunction "2_2") (pintype "passive"))
      (node (ref "D4") (pin "2") (pinfunction "A_2") (pintype "passive"))
      (node (ref "J2") (pin "23") (pinfunction "23_23") (pintype "passive"))
    )
    (net (code "17") (name "/RESE") (class "Default")
      (node (ref "J2") (pin "3") (pinfunction "3_3") (pintype "passive"))
      (node (ref "R13") (pin "1") (pinfunction "1_1") (pintype "passive"))
    )
    (net (code "18") (name "/SENS_SCL") (class "Default")
      (node (ref "R10") (pin "1") (pinfunction "1_1") (pintype "passive"))
      (node (ref "U3") (pin "7") (pinfunction "SCL_7") (pintype "input"))
      (node (ref "U4") (pin "4") (pinfunction "SCK_4") (pintype "input"))
      (node (ref "U5") (pin "14") (pinfunction "GPIO8_14") (pintype "bidirectional"))
    )
    (net (code "19") (name "/SENS_SDA") (class "Default")
      (node (ref "R9") (pin "1") (pinfunction "1_1") (pintype "passive"))
      (node (ref "U3") (pin "8") (pinfunction "SDA_8") (pintype "bidirectional"))
      (node (ref "U4") (pin "3") (pinfunction "SDI_3") (pintype "bidirectional"))
      (node (ref "U5") (pin "6") (pinfunction "GPIO2_6") (pintype "bidirectional"))
    )
    (net (code "20") (name "/USB_N") (class "Default")
      (node (ref "C7") (pin "1") (pinfunction "1_1") (pintype "passive"))
      (node (ref "R8") (pin "2") (pinfunction "2_2") (pintype "passive"))
      (node (ref "U5") (pin "26") (pinfunction "GPIO19_26") (pintype "passive"))
    )
    (net (code "21") (name "/USB_P") (class "Default")
      (node (ref "C5") (pin "1") (pinfunction "1_1") (pintype "passive"))
      (node (ref "R6") (pin "2") (pinfunction "2_2") (pintype "passive"))
      (node (ref "U5") (pin "25") (pinfunction "GPIO18_25") (pintype "passive"))
    )
    (net (code "22") (name "/XTAL_32K_N") (class "Default")
      (node (ref "C36") (pin "1") (pinfunction "1_1") (pintype "passive"))
      (node (ref "U5") (pin "5") (pinfunction "XTAL_32K_N_5") (pintype "bidirectional"))
      (node (ref "Y1") (pin "2") (pinfunction "2_2") (pintype "passive"))
    )
    (net (code "23") (name "/XTAL_32K_P") (class "Default")
      (node (ref "C35") (pin "1") (pinfunction "1_1") (pintype "passive"))
      (node (ref "U5") (pin "4") (pinfunction "XTAL_32K_P_4") (pintype "bidirectional"))
      (node (ref "Y1") (pin "1") (pinfunction "1_1") (pintype "passive"))
    )
    (net (code "24") (name "/XTAL_N") (class "Default")
      (node (ref "C34") (pin "1") (pinfunction "1_1") (pintype "passive"))
      (node (ref "U5") (pin "29") (pinfunction "XTAL_N_29") (pintype "output"))
      (node (ref "Y2") (pin "3") (pinfunction "3_3") (pintype "passive"))
    )
    (net (code "25") (name "/XTAL_P") (class "Default")
      (node (ref "C33") (pin "1") (pinfunction "1_1") (pintype "passive"))
      (node (ref "U5") (pin "30") (pinfunction "XTAL_P_30") (pintype "input"))
      (node (ref "Y2") (pin "1") (pinfunction "1_1") (pintype "passive"))
    )
    (net (code "26") (name "/~{ALRT}") (class "Default")
      (node (ref "R15") (pin "1") (pinfunction "1_1") (pintype "passive"))
      (node (ref "U3") (pin "5") (pinfunction "~{ALRT}_5") (pintype "open_collector"))
      (node (ref "U5") (pin "8") (pinfunction "GPIO3_8") (pintype "bidirectional"))
    )
    (net (code "27") (name "GND") (class "Default")
      (node (ref "C1") (pin "2") (pinfunction "2_2") (pintype "passive"))
      (node (ref "C10") (pin "2") (pinfunction "2_2") (pintype "passive"))
      (node (ref "C11") (pin "2") (pinfunction "2_2") (pintype "passive"))
      (node (ref "C12") (pin "2") (pinfunction "2_2") (pintype "passive"))
      (node (ref "C13") (pin "2") (pinfunction "2_2") (pintype "passive"))
      (node (ref "C14") (pin "2") (pinfunction "2_2") (pintype "passive"))
      (node (ref "C15") (pin "2") (pinfunction "2_2") (pintype "passive"))
      (node (ref "C16") (pin "2") (pinfunction "2_2") (pintype "passive"))
      (node (ref "C17") (pin "2") (pinfunction "2_2") (pintype "passive"))
      (node (ref "C18") (pin "2") (pinfunction "2_2") (pintype "passive"))
      (node (ref "C19") (pin "1") (pinfunction "1_1") (pintype "passive"))
      (node (ref "C2") (pin "2") (pinfunction "2_2") (pintype "passive"))
      (node (ref "C20") (pin "2") (pinfunction "2_2") (pintype "passive"))
      (node (ref "C21") (pin "2") (pinfunction "2_2") (pintype "passive"))
      (node (ref "C22") (pin "2") (pinfunction "2_2") (pintype "passive"))
      (node (ref "C23") (pin "1") (pinfunction "1_1") (pintype "passive"))
      (node (ref "C24") (pin "1") (pinfunction "1_1") (pintype "passive"))
      (node (ref "C25") (pin "1") (pinfunction "1_1") (pintype "passive"))
      (node (ref "C27") (pin "1") (pinfunction "1_1") (pintype "passive"))
      (node (ref "C28") (pin "2") (pinfunction "2_2") (pintype "passive"))
      (node (ref "C29") (pin "1") (pinfunction "1_1") (pintype "passive"))
      (node (ref "C3") (pin "2") (pinfunction "2_2") (pintype "passive"))
      (node (ref "C30") (pin "1") (pinfunction "1_1") (pintype "passive"))
      (node (ref "C31") (pin "2") (pinfunction "2_2") (pintype "passive"))
      (node (ref "C32") (pin "1") (pinfunction "1_1") (pintype "passive"))
      (node (ref "C33") (pin "2") (pinfunction "2_2") (pintype "passive"))
      (node (ref "C34") (pin "2") (pinfunction "2_2") (pintype "passive"))
      (node (ref "C35") (pin "2") (pinfunction "2_2") (pintype "passive"))
      (node (ref "C36") (pin "2") (pinfunction "2_2") (pintype "passive"))
      (node (ref "C37") (pin "2") (pinfunction "2_2") (pintype "passive"))
      (node (ref "C39") (pin "1") (pinfunction "1_1") (pintype "passive"))
      (node (ref "C4") (pin "2") (pinfunction "2_2") (pintype "passive"))
      (node (ref "C5") (pin "2") (pinfunction "2_2") (pintype "passive"))
      (node (ref "C6") (pin "1") (pinfunction "1_1") (pintype "passive"))
      (node (ref "C7") (pin "2") (pinfunction "2_2") (pintype "passive"))
      (node (ref "C8") (pin "2") (pinfunction "2_2") (pintype "passive"))
      (node (ref "C9") (pin "2") (pinfunction "2_2") (pintype "passive"))
      (node (ref "D3") (pin "1") (pinfunction "K_1") (pintype "passive"))
      (node (ref "D6") (pin "1") (pinfunction "C_1") (pintype "passive"))
      (node (ref "J1") (pin "1") (pinfunction "1_MID_1") (pintype "passive"))
      (node (ref "J1") (pin "2") (pinfunction "2_MID_2") (pintype "passive"))
      (node (ref "J1") (pin "3") (pinfunction "MNT_1_3") (pintype "passive"))
      (node (ref "J1") (pin "4") (pinfunction "MNT_2_4") (pintype "passive"))
      (node (ref "J1") (pin "5") (pinfunction "MNT_3_5") (pintype "passive"))
      (node (ref "J1") (pin "6") (pinfunction "MNT_4_6") (pintype "passive"))
      (node (ref "J1") (pin "A1") (pinfunction "GND_A1") (pintype "passive"))
      (node (ref "J1") (pin "A12") (pinfunction "GND_A12") (pintype "passive"))
      (node (ref "J1") (pin "B1") (pinfunction "GND_B1") (pintype "passive"))
      (node (ref "J1") (pin "B12") (pinfunction "GND_B12") (pintype "passive"))
      (node (ref "J2") (pin "17") (pinfunction "17_17") (pintype "passive"))
      (node (ref "J2") (pin "8") (pinfunction "8_8") (pintype "passive"))
      (node (ref "J2") (pin "MP1") (pinfunction "MP1_MP1") (pintype "passive"))
      (node (ref "J2") (pin "MP2") (pinfunction "MP2_MP2") (pintype "passive"))
      (node (ref "L2") (pin "1") (pinfunction "1_1") (pintype "passive"))
      (node (ref "P1") (pin "2") (pinfunction "2_2") (pintype "passive"))
      (node (ref "P1") (pin "MP1") (pinfunction "MP1_MP1") (pintype "passive"))
      (node (ref "P1") (pin "MP2") (pinfunction "MP2_MP2") (pintype "passive"))
      (node (ref "Q2") (pin "2") (pinfunction "S_2") (pintype "passive"))
      (node (ref "R1") (pin "2") (pinfunction "2_2") (pintype "passive"))
      (node (ref "R12") (pin "1") (pinfunction "1_1") (pintype "passive"))
      (node (ref "R13") (pin "2") (pinfunction "2_2") (pintype "passive"))
      (node (ref "R3") (pin "2") (pinfunction "2_2") (pintype "passive"))
      (node (ref "R4") (pin "1") (pinfunction "1_1") (pintype "passive"))
      (node (ref "R5") (pin "1") (pinfunction "1_1") (pintype "passive"))
      (node (ref "SW1") (pin "2") (pinfunction "2_2") (pintype "passive"))
      (node (ref "SW1") (pin "3") (pinfunction "GROUND_3") (pintype "passive"))
      (node (ref "SW1") (pin "4") (pinfunction "GROUND_4") (pintype "passive"))
      (node (ref "SW2") (pin "2") (pinfunction "2_2") (pintype "passive"))
      (node (ref "SW2") (pin "3") (pinfunction "GROUND_3") (pintype "passive"))
      (node (ref "SW2") (pin "4") (pinfunction "GROUND_4") (pintype "passive"))
      (node (ref "U1") (pin "2") (pinfunction "GND_2") (pintype "passive"))
      (node (ref "U2") (pin "2") (pinfunction "VSS_2") (pintype "passive"))
      (node (ref "U3") (pin "1") (pinfunction "CTG_1") (pintype "power_in"))
      (node (ref "U3") (pin "4") (pinfunction "GND_4") (pintype "passive"))
      (node (ref "U3") (pin "6") (pinfunction "QSTRT_6") (pintype "input"))
      (node (ref "U3") (pin "9") (pinfunction "EP_9") (pintype "passive"))
      (node (ref "U4") (pin "1") (pinfunction "GND_1") (pintype "passive"))
      (node (ref "U4") (pin "5") (pinfunction "SDO_5") (pintype "passive"))
      (node (ref "U4") (pin "7") (pinfunction "GND_7") (pintype "passive"))
      (node (ref "U5") (pin "33") (pinfunction "GND_33") (pintype "power_in"))
      (node (ref "Y2") (pin "2") (pinfunction "GND_2") (pintype "passive"))
      (node (ref "Y2") (pin "4") (pinfunction "GND_4") (pintype "passive"))
    )
    (net (code "28") (name "Net-(ANT1-FEED)") (class "Default")
      (node (ref "ANT1") (pin "1") (pinfunction "FEED_1") (pintype "passive"))
      (node (ref "L1") (pin "2") (pinfunction "2_2") (pintype "passive"))
    )
    (net (code "29") (name "Net-(C19-Pad2)") (class "Default")
      (node (ref "C19") (pin "2") (pinfunction "2_2") (pintype "passive"))
      (node (ref "J2") (pin "5") (pinfunction "5_5") (pintype "passive"))
    )
    (net (code "30") (name "Net-(C23-Pad2)") (class "Default")
      (node (ref "C23") (pin "2") (pinfunction "2_2") (pintype "passive"))
      (node (ref "J2") (pin "18") (pinfunction "18_18") (pintype "passive"))
    )
    (net (code "31") (name "Net-(C24-Pad2)") (class "Default")
      (node (ref "C24") (pin "2") (pinfunction "2_2") (pintype "passive"))
      (node (ref "J2") (pin "19") (pinfunction "19_19") (pintype "passive"))
    )
    (net (code "32") (name "Net-(C25-Pad2)") (class "Default")
      (node (ref "C25") (pin "2") (pinfunction "2_2") (pintype "passive"))
      (node (ref "J2") (pin "20") (pinfunction "20_20") (pintype "passive"))
    )
    (net (code "33") (name "Net-(C27-Pad2)") (class "Default")
      (node (ref "C27") (pin "2") (pinfunction "2_2") (pintype "passive"))
      (node (ref "J2") (pin "22") (pinfunction "22_22") (pintype "passive"))
    )
    (net (code "34") (name "Net-(C30-Pad2)") (class "Default")
      (node (ref "C30") (pin "2") (pinfunction "2_2") (pintype "passive"))
      (node (ref "J2") (pin "24") (pinfunction "24_24") (pintype "passive"))
    )
    (net (code "35") (name "Net-(C38-Pad2)") (class "Default")
      (node (ref "C38") (pin "2") (pinfunction "2_2") (pintype "passive"))
      (node (ref "L1") (pin "1") (pinfunction "1_1") (pintype "passive"))
      (node (ref "L2") (pin "2") (pinfunction "2_2") (pintype "passive"))
    )
    (net (code "36") (name "Net-(C39-Pad2)") (class "Default")
      (node (ref "C39") (pin "2") (pinfunction "2_2") (pintype "passive"))
      (node (ref "J2") (pin "4") (pinfunction "4_4") (pintype "passive"))
    )
    (net (code "37") (name "Net-(D1-C)") (class "Default")
      (node (ref "C4") (pin "1") (pinfunction "1_1") (pintype "passive"))
      (node (ref "D1") (pin "1") (pinfunction "C_1") (pintype "passive"))
      (node (ref "Q1") (pin "2") (pinfunction "S_2") (pintype "passive"))
      (node (ref "U1") (pin "1") (pinfunction "IN_1") (pintype "power_in"))
      (node (ref "U1") (pin "3") (pinfunction "EN_3") (pintype "input"))
    )
    (net (code "38") (name "Net-(D2-K)") (class "Default")
      (node (ref "D2") (pin "1") (pinfunction "K_1") (pintype "passive"))
      (node (ref "R2") (pin "1") (pinfunction "1_1") (pintype "passive"))
    )
    (net (code "39") (name "Net-(D3-A)") (class "Default")
      (node (ref "D3") (pin "2") (pinfunction "A_2") (pintype "passive"))
      (node (ref "R7") (pin "1") (pinfunction "1_1") (pintype "passive"))
    )
    (net (code "40") (name "Net-(D4-C)") (class "Default")
      (node (ref "C26") (pin "2") (pinfunction "2_2") (pintype "passive"))
      (node (ref "D4") (pin "1") (pinfunction "C_1") (pintype "passive"))
      (node (ref "D6") (pin "2") (pinfunction "A_2") (pintype "passive"))
    )
    (net (code "41") (name "Net-(D5-A)") (class "Default")
      (node (ref "C26") (pin "1") (pinfunction "1_1") (pintype "passive"))
      (node (ref "D5") (pin "2") (pinfunction "A_2") (pintype "passive"))
      (node (ref "L4") (pin "2") (pinfunction "2_2") (pintype "passive"))
      (node (ref "Q2") (pin "3") (pinfunction "D_3") (pintype "passive"))
    )
    (net (code "42") (name "Net-(F1-Pad1)") (class "Default")
      (node (ref "F1") (pin "1") (pinfunction "1_1") (pintype "passive"))
      (node (ref "J1") (pin "A4") (pinfunction "VBUS_A4") (pintype "power_in"))
      (node (ref "J1") (pin "A9") (pinfunction "VBUS_A9") (pintype "power_in"))
      (node (ref "J1") (pin "B4") (pinfunction "VBUS_B4") (pintype "power_in"))
      (node (ref "J1") (pin "B9") (pinfunction "VBUS_B9") (pintype "power_in"))
    )
    (net (code "43") (name "Net-(J1-1_D+)") (class "Default")
      (node (ref "J1") (pin "A6") (pinfunction "1_D+_A6") (pintype "bidirectional"))
      (node (ref "J1") (pin "B6") (pinfunction "2_D+_B6") (pintype "bidirectional"))
      (node (ref "R6") (pin "1") (pinfunction "1_1") (pintype "passive"))
    )
    (net (code "44") (name "Net-(J1-1_D-)") (class "Default")
      (node (ref "J1") (pin "A7") (pinfunction "1_D-_A7") (pintype "bidirectional"))
      (node (ref "J1") (pin "B7") (pinfunction "2_D-_B7") (pintype "bidirectional"))
      (node (ref "R8") (pin "1") (pinfunction "1_1") (pintype "passive"))
    )
    (net (code "45") (name "Net-(J1-CC1)") (class "Default")
      (node (ref "J1") (pin "A5") (pinfunction "CC1_A5") (pintype "passive"))
      (node (ref "R1") (pin "1") (pinfunction "1_1") (pintype "passive"))
    )
    (net (code "46") (name "Net-(J1-CC2)") (class "Default")
      (node (ref "J1") (pin "B5") (pinfunction "CC2_B5") (pintype "passive"))
      (node (ref "R3") (pin "1") (pinfunction "1_1") (pintype "passive"))
    )
    (net (code "47") (name "Net-(U2-PROG)") (class "Default")
      (node (ref "R5") (pin "2") (pinfunction "2_2") (pintype "passive"))
      (node (ref "U2") (pin "5") (pinfunction "PROG_5") (pintype "passive"))
    )
    (net (code "48") (name "Net-(U2-STAT)") (class "Default")
      (node (ref "R2") (pin "2") (pinfunction "2_2") (pintype "passive"))
      (node (ref "R7") (pin "2") (pinfunction "2_2") (pintype "passive"))
      (node (ref "U2") (pin "1") (pinfunction "STAT_1") (pintype "passive"))
    )
    (net (code "49") (name "unconnected-(ANT1-NC-Pad2)") (class "Default")
      (node (ref "ANT1") (pin "2") (pinfunction "NC_2") (pintype "passive+no_connect"))
    )
    (net (code "50") (name "unconnected-(J1-SBU1-PadA8)") (class "Default")
      (node (ref "J1") (pin "A8") (pinfunction "SBU1_A8") (pintype "passive+no_connect"))
    )
    (net (code "51") (name "unconnected-(J1-SBU2-PadB8)") (class "Default")
      (node (ref "J1") (pin "B8") (pinfunction "SBU2_B8") (pintype "passive+no_connect"))
    )
    (net (code "52") (name "unconnected-(J2-Pad1)") (class "Default")
      (node (ref "J2") (pin "1") (pinfunction "1_1") (pintype "passive+no_connect"))
    )
    (net (code "53") (name "unconnected-(J2-Pad6)") (class "Default")
      (node (ref "J2") (pin "6") (pinfunction "6_6") (pintype "passive+no_connect"))
    )
    (net (code "54") (name "unconnected-(J2-Pad7)") (class "Default")
      (node (ref "J2") (pin "7") (pinfunction "7_7") (pintype "passive+no_connect"))
    )
    (net (code "55") (name "unconnected-(U1-NC-Pad4)") (class "Default")
      (node (ref "U1") (pin "4") (pinfunction "NC_4") (pintype "passive+no_connect"))
    )
    (net (code "56") (name "unconnected-(U5-SPICLK-Pad22)") (class "Default")
      (node (ref "U5") (pin "22") (pinfunction "SPICLK_22") (pintype "bidirectional+no_connect"))
    )
    (net (code "57") (name "unconnected-(U5-SPICS0-Pad21)") (class "Default")
      (node (ref "U5") (pin "21") (pinfunction "SPICS0_21") (pintype "bidirectional+no_connect"))
    )
    (net (code "58") (name "unconnected-(U5-SPID-Pad23)") (class "Default")
      (node (ref "U5") (pin "23") (pinfunction "SPID_23") (pintype "bidirectional+no_connect"))
    )
    (net (code "59") (name "unconnected-(U5-SPIHD-Pad19)") (class "Default")
      (node (ref "U5") (pin "19") (pinfunction "SPIHD_19") (pintype "bidirectional+no_connect"))
    )
    (net (code "60") (name "unconnected-(U5-SPIQ-Pad24)") (class "Default")
      (node (ref "U5") (pin "24") (pinfunction "SPIQ_24") (pintype "bidirectional+no_connect"))
    )
    (net (code "61") (name "unconnected-(U5-SPIWP-Pad20)") (class "Default")
      (node (ref "U5") (pin "20") (pinfunction "SPIWP_20") (pintype "bidirectional+no_connect"))
    )
    (net (code "62") (name "unconnected-(U5-U0TXD-Pad28)") (class "Default")
      (node (ref "U5") (pin "28") (pinfunction "U0TXD_28") (pintype "bidirectional+no_connect"))
    )
  )
)
